# PSU_SET_3V3.net
KiCad netlist of a schematic drawn in Altium Designer
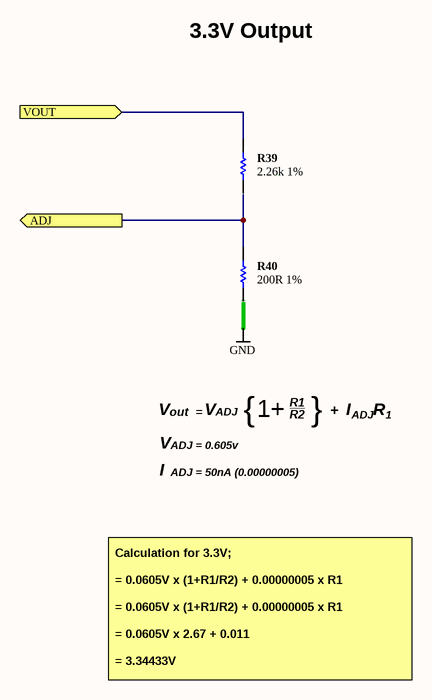
[diagram p0: PSU_SET_3V3.SchDoc]

(export (version "E")
  (design (tool "Eeschema 10.0.6"))
  (components
    (comp (ref "R39")
      (value "2.26k 1%")
      (footprint "RESC1005-STAR")
      (description "Resistor, 120R 1% 0402 (1005)")
      (fields (field (name "TOLERANCE") "1 %"))
      (libsource (lib "AltiumDesignLibrary") (part "RES"))
    )
    (comp (ref "R40")
      (value "200R 1%")
      (footprint "RESC1005-STAR")
      (description "Resistor, 200R 1% 0402 (1005)")
      (fields (field (name "TOLERANCE") "1 %"))
      (libsource (lib "AltiumDesignLibrary") (part "RES"))
    )
  )
  (nets
    (net (code "1") (name "/ADJ") (class "Default")
      (node (ref "R39") (pin "1") (pinfunction "1_1") (pintype "passive"))
      (node (ref "R40") (pin "1") (pinfunction "1_1") (pintype "passive"))
    )
    (net (code "2") (name "/VOUT") (class "Default")
      (node (ref "R39") (pin "2") (pinfunction "2_2") (pintype "passive"))
    )
    (net (code "3") (name "GND") (class "Default")
      (node (ref "R40") (pin "2") (pinfunction "2_2") (pintype "passive"))
    )
  )
)
